# sensor_enco.net
KiCad netlist of a schematic drawn in EAGLE
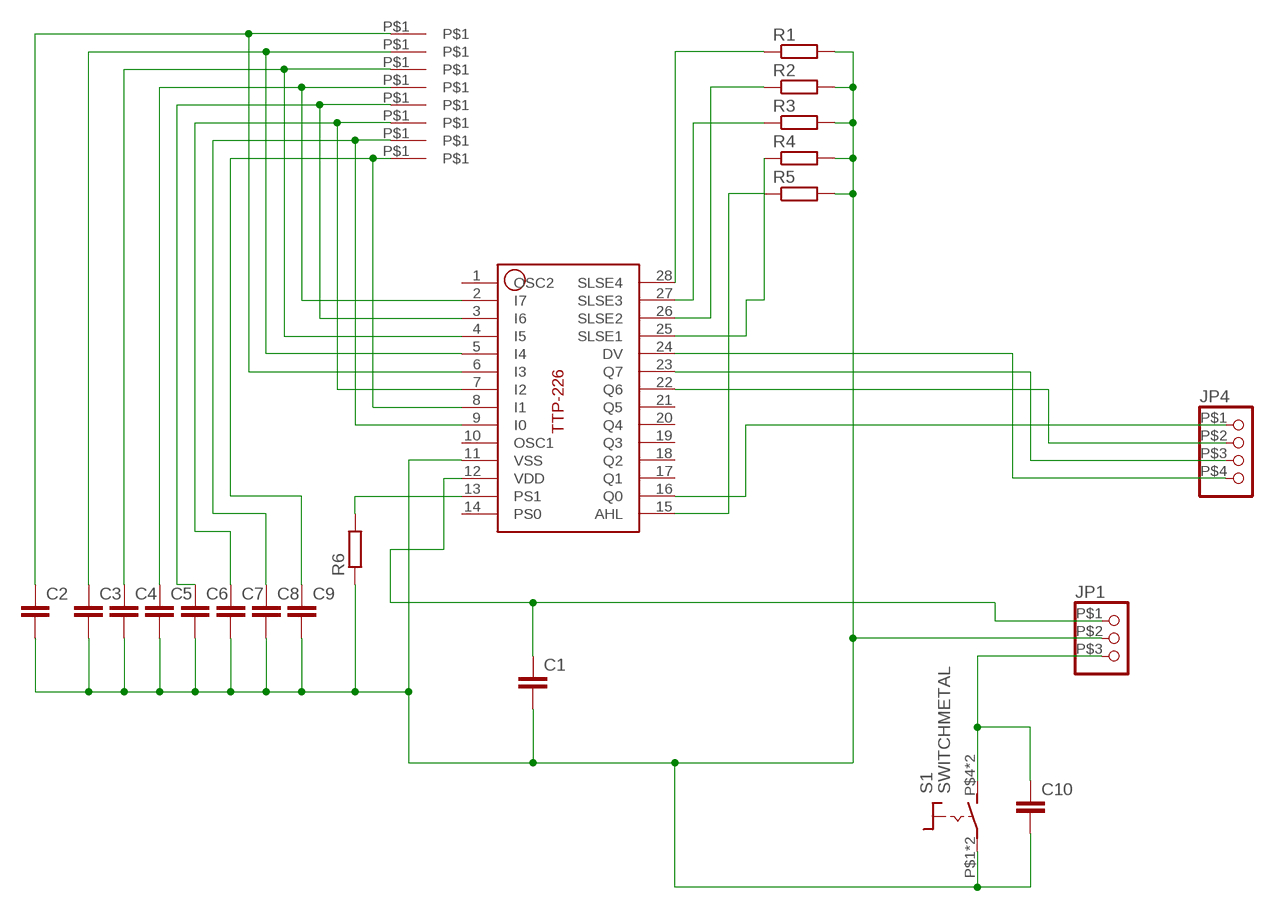
[diagram p0: schematic, sheet 1]

(export (version "E")
  (design (tool "Eeschema 10.0.6"))
  (components
    (comp (ref "C1")
      (value "C-EUC0402")
      (footprint "eagle-import:C0402")
      (libsource (lib "eagle-import") (part "C-EUC0402"))
    )
    (comp (ref "C2")
      (value "C-EUC0402")
      (footprint "eagle-import:C0402")
      (libsource (lib "eagle-import") (part "C-EUC0402"))
    )
    (comp (ref "C3")
      (value "C-EUC0402")
      (footprint "eagle-import:C0402")
      (libsource (lib "eagle-import") (part "C-EUC0402"))
    )
    (comp (ref "C4")
      (value "C-EUC0402")
      (footprint "eagle-import:C0402")
      (libsource (lib "eagle-import") (part "C-EUC0402"))
    )
    (comp (ref "C5")
      (value "C-EUC0402")
      (footprint "eagle-import:C0402")
      (libsource (lib "eagle-import") (part "C-EUC0402"))
    )
    (comp (ref "C6")
      (value "C-EUC0402")
      (footprint "eagle-import:C0402")
      (libsource (lib "eagle-import") (part "C-EUC0402"))
    )
    (comp (ref "C7")
      (value "C-EUC0402")
      (footprint "eagle-import:C0402")
      (libsource (lib "eagle-import") (part "C-EUC0402"))
    )
    (comp (ref "C8")
      (value "C-EUC0402")
      (footprint "eagle-import:C0402")
      (libsource (lib "eagle-import") (part "C-EUC0402"))
    )
    (comp (ref "C9")
      (value "C-EUC0402")
      (footprint "eagle-import:C0402")
      (libsource (lib "eagle-import") (part "C-EUC0402"))
    )
    (comp (ref "C10")
      (value "C-EUC0402")
      (footprint "eagle-import:C0402")
      (libsource (lib "eagle-import") (part "C-EUC0402"))
    )
    (comp (ref "JP1")
      (value "PINHD-1X32MM")
      (footprint "eagle-import:1X03_2MM")
      (libsource (lib "eagle-import") (part "PINHD-1X32MM"))
    )
    (comp (ref "JP4")
      (value "PINHD-1X42MM")
      (footprint "eagle-import:1X04_2MM")
      (libsource (lib "eagle-import") (part "PINHD-1X42MM"))
    )
    (comp (ref "R1")
      (value "R-EU_R0402")
      (footprint "eagle-import:R0402")
      (libsource (lib "eagle-import") (part "R-EU_R0402"))
    )
    (comp (ref "R2")
      (value "R-EU_R0402")
      (footprint "eagle-import:R0402")
      (libsource (lib "eagle-import") (part "R-EU_R0402"))
    )
    (comp (ref "R3")
      (value "R-EU_R0402")
      (footprint "eagle-import:R0402")
      (libsource (lib "eagle-import") (part "R-EU_R0402"))
    )
    (comp (ref "R4")
      (value "R-EU_R0402")
      (footprint "eagle-import:R0402")
      (libsource (lib "eagle-import") (part "R-EU_R0402"))
    )
    (comp (ref "R5")
      (value "R-EU_R0402")
      (footprint "eagle-import:R0402")
      (libsource (lib "eagle-import") (part "R-EU_R0402"))
    )
    (comp (ref "R6")
      (value "R-EU_R0402")
      (footprint "eagle-import:R0402")
      (libsource (lib "eagle-import") (part "R-EU_R0402"))
    )
    (comp (ref "S1")
      (value "SWITCHMETAL")
      (footprint "eagle-import:SWMET")
      (libsource (lib "eagle-import") (part "SWITCHMETAL"))
    )
    (comp (ref "U$1")
      (value "SENSOR_PADSENSORPAD3")
      (footprint "eagle-import:SENSOR_PAD3")
      (libsource (lib "eagle-import") (part "SENSOR_PADSENSORPAD3"))
    )
    (comp (ref "U$2")
      (value "SENSOR_PADSENSORPAD3")
      (footprint "eagle-import:SENSOR_PAD3")
      (libsource (lib "eagle-import") (part "SENSOR_PADSENSORPAD3"))
    )
    (comp (ref "U$9")
      (value "TTP-226LIBTOUCH-TTP226")
      (footprint "eagle-import:TSSOP28")
      (libsource (lib "eagle-import") (part "TTP-226LIBTOUCH-TTP226"))
    )
    (comp (ref "U$10")
      (value "SENSOR_PADSENSORPAD3")
      (footprint "eagle-import:SENSOR_PAD3")
      (libsource (lib "eagle-import") (part "SENSOR_PADSENSORPAD3"))
    )
    (comp (ref "U$11")
      (value "SENSOR_PADSENSORPAD3")
      (footprint "eagle-import:SENSOR_PAD3")
      (libsource (lib "eagle-import") (part "SENSOR_PADSENSORPAD3"))
    )
    (comp (ref "U$12")
      (value "SENSOR_PADSENSORPAD3")
      (footprint "eagle-import:SENSOR_PAD3")
      (libsource (lib "eagle-import") (part "SENSOR_PADSENSORPAD3"))
    )
    (comp (ref "U$13")
      (value "SENSOR_PADSENSORPAD3")
      (footprint "eagle-import:SENSOR_PAD3")
      (libsource (lib "eagle-import") (part "SENSOR_PADSENSORPAD3"))
    )
    (comp (ref "U$14")
      (value "SENSOR_PADSENSORPAD3")
      (footprint "eagle-import:SENSOR_PAD3")
      (libsource (lib "eagle-import") (part "SENSOR_PADSENSORPAD3"))
    )
    (comp (ref "U$15")
      (value "SENSOR_PADSENSORPAD3")
      (footprint "eagle-import:SENSOR_PAD3")
      (libsource (lib "eagle-import") (part "SENSOR_PADSENSORPAD3"))
    )
  )
  (nets
    (net (code "1") (name "Net-(JP1-1)") (class "Default")
      (node (ref "C1") (pin "1") (pinfunction "1_1") (pintype "passive"))
      (node (ref "JP1") (pin "P$1") (pinfunction "1_P$1") (pintype "passive"))
      (node (ref "U$9") (pin "12") (pinfunction "VDD_12") (pintype "power_in"))
    )
    (net (code "2") (name "Net-(JP1-2)") (class "Default")
      (node (ref "C1") (pin "2") (pinfunction "2_2") (pintype "passive"))
      (node (ref "C10") (pin "2") (pinfunction "2_2") (pintype "passive"))
      (node (ref "C2") (pin "2") (pinfunction "2_2") (pintype "passive"))
      (node (ref "C3") (pin "2") (pinfunction "2_2") (pintype "passive"))
      (node (ref "C4") (pin "2") (pinfunction "2_2") (pintype "passive"))
      (node (ref "C5") (pin "2") (pinfunction "2_2") (pintype "passive"))
      (node (ref "C6") (pin "2") (pinfunction "2_2") (pintype "passive"))
      (node (ref "C7") (pin "2") (pinfunction "2_2") (pintype "passive"))
      (node (ref "C8") (pin "2") (pinfunction "2_2") (pintype "passive"))
      (node (ref "C9") (pin "2") (pinfunction "2_2") (pintype "passive"))
      (node (ref "JP1") (pin "P$2") (pinfunction "2_P$2") (pintype "passive"))
      (node (ref "R1") (pin "2") (pinfunction "2_2") (pintype "passive"))
      (node (ref "R2") (pin "2") (pinfunction "2_2") (pintype "passive"))
      (node (ref "R3") (pin "2") (pinfunction "2_2") (pintype "passive"))
      (node (ref "R4") (pin "2") (pinfunction "2_2") (pintype "passive"))
      (node (ref "R5") (pin "2") (pinfunction "2_2") (pintype "passive"))
      (node (ref "R6") (pin "1") (pinfunction "1_1") (pintype "passive"))
      (node (ref "S1") (pin "P$1") (pinfunction "P_P$1") (pintype "passive"))
      (node (ref "S1") (pin "P$1@1") (pinfunction "P_P$1@1") (pintype "passive"))
      (node (ref "U$9") (pin "11") (pinfunction "VSS_11") (pintype "power_in"))
    )
    (net (code "3") (name "Net-(JP1-3)") (class "Default")
      (node (ref "C10") (pin "1") (pinfunction "1_1") (pintype "passive"))
      (node (ref "JP1") (pin "P$3") (pinfunction "3_P$3") (pintype "passive"))
      (node (ref "S1") (pin "P$4") (pinfunction "S_P$4") (pintype "passive"))
      (node (ref "S1") (pin "P$4@1") (pinfunction "S_P$4@1") (pintype "passive"))
    )
    (net (code "4") (name "Net-(JP4-1)") (class "Default")
      (node (ref "JP4") (pin "P$1") (pinfunction "1_P$1") (pintype "passive"))
      (node (ref "U$9") (pin "16") (pinfunction "Q0_16") (pintype "output"))
    )
    (net (code "5") (name "Net-(JP4-2)") (class "Default")
      (node (ref "JP4") (pin "P$2") (pinfunction "2_P$2") (pintype "passive"))
      (node (ref "U$9") (pin "22") (pinfunction "Q6_22") (pintype "output"))
    )
    (net (code "6") (name "Net-(JP4-3)") (class "Default")
      (node (ref "JP4") (pin "P$3") (pinfunction "3_P$3") (pintype "passive"))
      (node (ref "U$9") (pin "23") (pinfunction "Q7_23") (pintype "output"))
    )
    (net (code "7") (name "Net-(JP4-4)") (class "Default")
      (node (ref "JP4") (pin "P$4") (pinfunction "4_P$4") (pintype "passive"))
      (node (ref "U$9") (pin "24") (pinfunction "DV_24") (pintype "tri_state"))
    )
    (net (code "8") (name "Net-(U$9-AHL)") (class "Default")
      (node (ref "R5") (pin "1") (pinfunction "1_1") (pintype "passive"))
      (node (ref "U$9") (pin "15") (pinfunction "AHL_15") (pintype "passive"))
    )
    (net (code "9") (name "Net-(U$9-I0)") (class "Default")
      (node (ref "C8") (pin "1") (pinfunction "1_1") (pintype "passive"))
      (node (ref "U$14") (pin "P$1") (pinfunction "P$1_P$1") (pintype "bidirectional"))
      (node (ref "U$9") (pin "9") (pinfunction "I0_9") (pintype "input"))
    )
    (net (code "10") (name "Net-(U$9-I1)") (class "Default")
      (node (ref "C9") (pin "1") (pinfunction "1_1") (pintype "passive"))
      (node (ref "U$15") (pin "P$1") (pinfunction "P$1_P$1") (pintype "bidirectional"))
      (node (ref "U$9") (pin "8") (pinfunction "I1_8") (pintype "input"))
    )
    (net (code "11") (name "Net-(U$9-I2)") (class "Default")
      (node (ref "C7") (pin "1") (pinfunction "1_1") (pintype "passive"))
      (node (ref "U$13") (pin "P$1") (pinfunction "P$1_P$1") (pintype "bidirectional"))
      (node (ref "U$9") (pin "7") (pinfunction "I2_7") (pintype "input"))
    )
    (net (code "12") (name "Net-(U$9-I3)") (class "Default")
      (node (ref "C2") (pin "1") (pinfunction "1_1") (pintype "passive"))
      (node (ref "U$1") (pin "P$1") (pinfunction "P$1_P$1") (pintype "bidirectional"))
      (node (ref "U$9") (pin "6") (pinfunction "I3_6") (pintype "input"))
    )
    (net (code "13") (name "Net-(U$9-I4)") (class "Default")
      (node (ref "C3") (pin "1") (pinfunction "1_1") (pintype "passive"))
      (node (ref "U$2") (pin "P$1") (pinfunction "P$1_P$1") (pintype "bidirectional"))
      (node (ref "U$9") (pin "5") (pinfunction "I4_5") (pintype "input"))
    )
    (net (code "14") (name "Net-(U$9-I5)") (class "Default")
      (node (ref "C4") (pin "1") (pinfunction "1_1") (pintype "passive"))
      (node (ref "U$10") (pin "P$1") (pinfunction "P$1_P$1") (pintype "bidirectional"))
      (node (ref "U$9") (pin "4") (pinfunction "I5_4") (pintype "input"))
    )
    (net (code "15") (name "Net-(U$9-I6)") (class "Default")
      (node (ref "C6") (pin "1") (pinfunction "1_1") (pintype "passive"))
      (node (ref "U$12") (pin "P$1") (pinfunction "P$1_P$1") (pintype "bidirectional"))
      (node (ref "U$9") (pin "3") (pinfunction "I6_3") (pintype "input"))
    )
    (net (code "16") (name "Net-(U$9-I7)") (class "Default")
      (node (ref "C5") (pin "1") (pinfunction "1_1") (pintype "passive"))
      (node (ref "U$11") (pin "P$1") (pinfunction "P$1_P$1") (pintype "bidirectional"))
      (node (ref "U$9") (pin "2") (pinfunction "I7_2") (pintype "input"))
    )
    (net (code "17") (name "Net-(U$9-PS1)") (class "Default")
      (node (ref "R6") (pin "2") (pinfunction "2_2") (pintype "passive"))
      (node (ref "U$9") (pin "13") (pinfunction "PS1_13") (pintype "passive"))
    )
    (net (code "18") (name "Net-(U$9-SLSE1)") (class "Default")
      (node (ref "R4") (pin "1") (pinfunction "1_1") (pintype "passive"))
      (node (ref "U$9") (pin "25") (pinfunction "SLSE1_25") (pintype "passive"))
    )
    (net (code "19") (name "Net-(U$9-SLSE2)") (class "Default")
      (node (ref "R2") (pin "1") (pinfunction "1_1") (pintype "passive"))
      (node (ref "U$9") (pin "26") (pinfunction "SLSE2_26") (pintype "passive"))
    )
    (net (code "20") (name "Net-(U$9-SLSE3)") (class "Default")
      (node (ref "R3") (pin "1") (pinfunction "1_1") (pintype "passive"))
      (node (ref "U$9") (pin "27") (pinfunction "SLSE3_27") (pintype "passive"))
    )
    (net (code "21") (name "Net-(U$9-SLSE4)") (class "Default")
      (node (ref "R1") (pin "1") (pinfunction "1_1") (pintype "passive"))
      (node (ref "U$9") (pin "28") (pinfunction "SLSE4_28") (pintype "passive"))
    )
    (net (code "22") (name "unconnected-(U$9-OSC1-Pad10)") (class "Default")
      (node (ref "U$9") (pin "10") (pinfunction "OSC1_10") (pintype "open_collector"))
    )
    (net (code "23") (name "unconnected-(U$9-OSC2-Pad1)") (class "Default")
      (node (ref "U$9") (pin "1") (pinfunction "OSC2_1") (pintype "bidirectional"))
    )
    (net (code "24") (name "unconnected-(U$9-PS0-Pad14)") (class "Default")
      (node (ref "U$9") (pin "14") (pinfunction "PS0_14") (pintype "passive"))
    )
    (net (code "25") (name "unconnected-(U$9-Q1-Pad17)") (class "Default")
      (node (ref "U$9") (pin "17") (pinfunction "Q1_17") (pintype "output"))
    )
    (net (code "26") (name "unconnected-(U$9-Q2-Pad18)") (class "Default")
      (node (ref "U$9") (pin "18") (pinfunction "Q2_18") (pintype "output"))
    )
    (net (code "27") (name "unconnected-(U$9-Q3-Pad19)") (class "Default")
      (node (ref "U$9") (pin "19") (pinfunction "Q3_19") (pintype "output"))
    )
    (net (code "28") (name "unconnected-(U$9-Q4-Pad20)") (class "Default")
      (node (ref "U$9") (pin "20") (pinfunction "Q4_20") (pintype "output"))
    )
    (net (code "29") (name "unconnected-(U$9-Q5-Pad21)") (class "Default")
      (node (ref "U$9") (pin "21") (pinfunction "Q5_21") (pintype "output"))
    )
  )
)
